# nrf24wifidongle.net
KiCad netlist of a schematic drawn in EAGLE
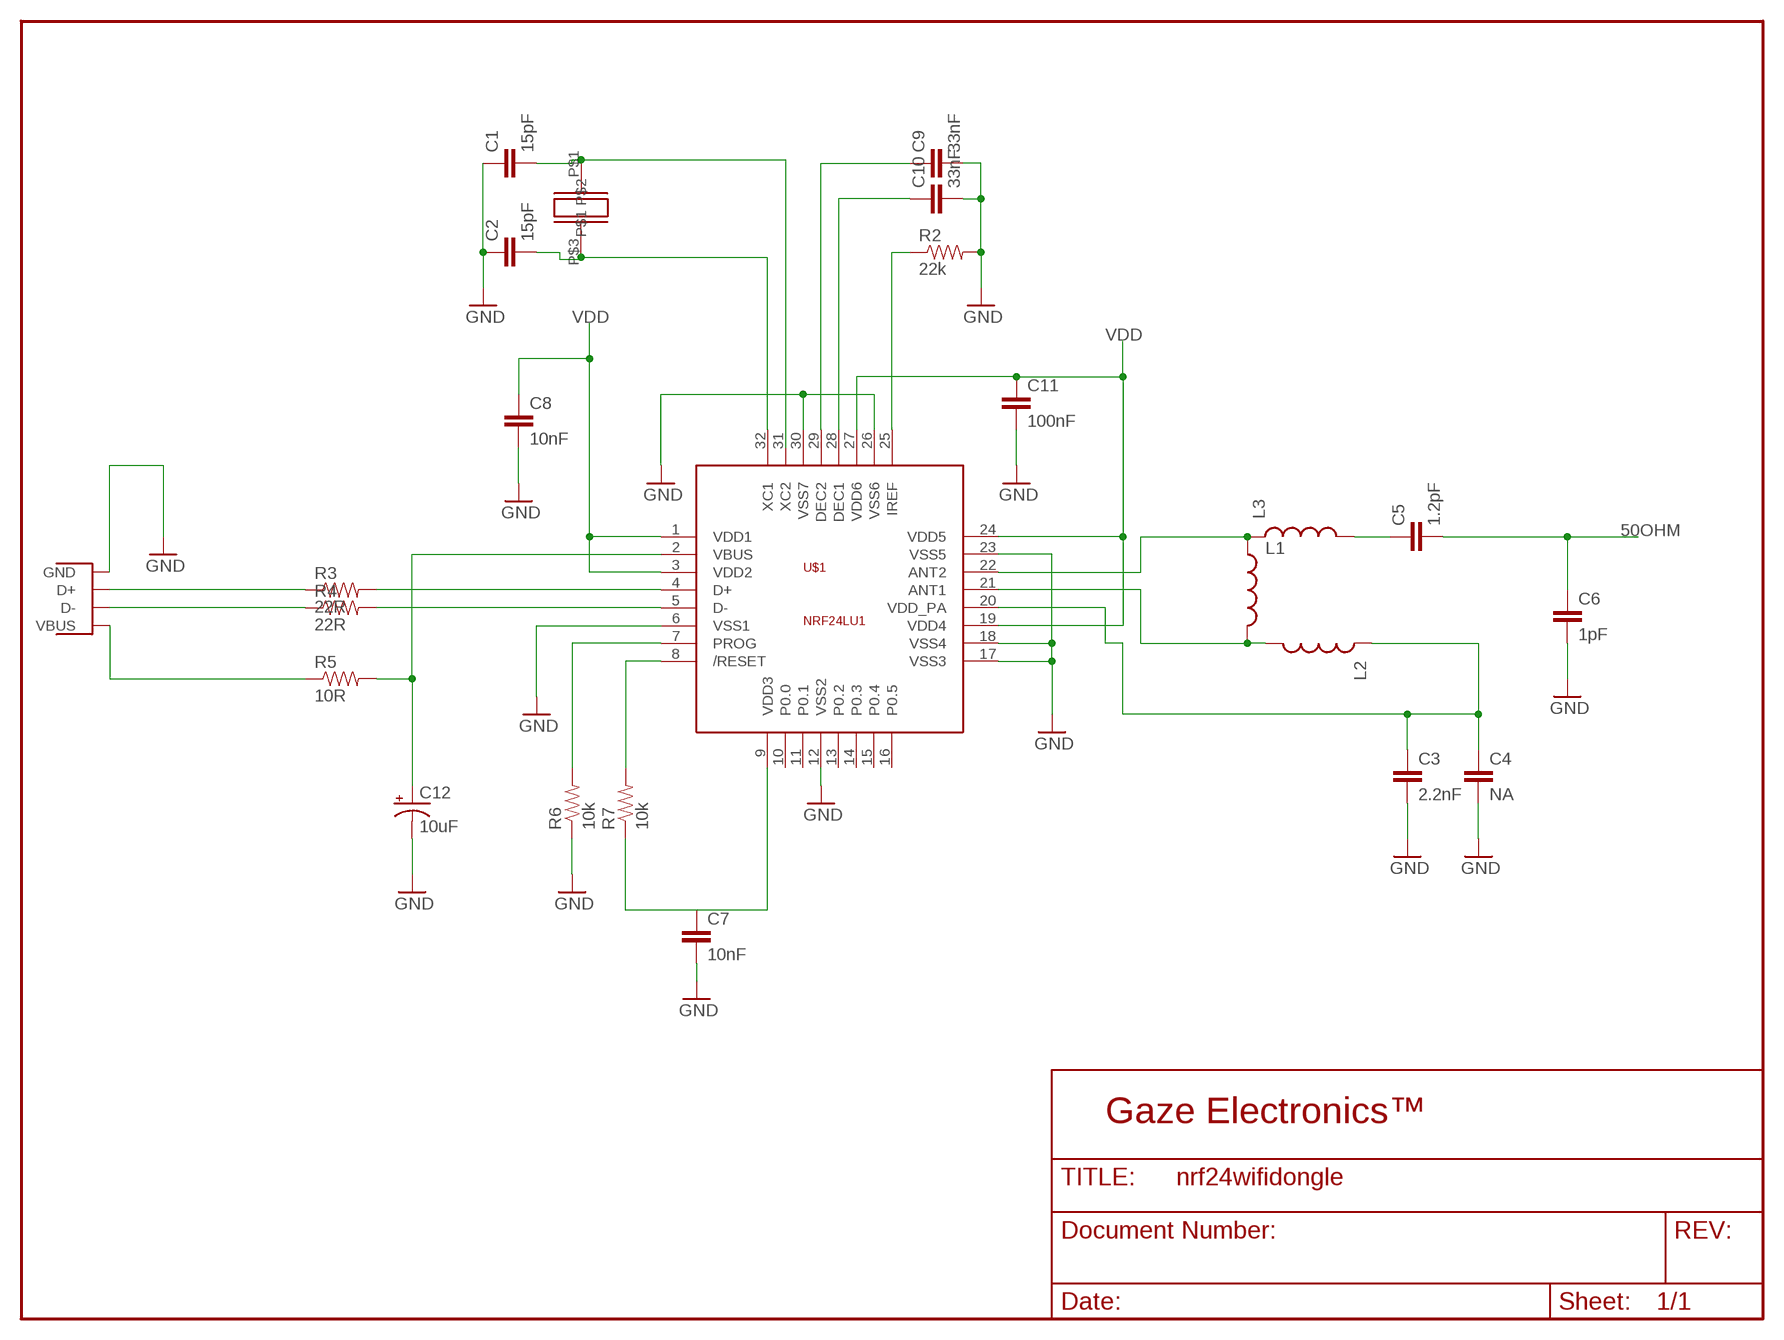
[diagram p0: schematic, sheet 1]

(export (version "E")
  (design (tool "Eeschema 10.0.6"))
  (components
    (comp (ref "C1")
      (value "15pF")
      (footprint "eagle-import:C0402")
      (libsource (lib "eagle-import") (part "CAP0402"))
    )
    (comp (ref "C2")
      (value "15pF")
      (footprint "eagle-import:C0402")
      (libsource (lib "eagle-import") (part "CAP0402"))
    )
    (comp (ref "C3")
      (value "2.2nF")
      (footprint "eagle-import:C0402")
      (libsource (lib "eagle-import") (part "CAP0402"))
    )
    (comp (ref "C4")
      (value "NA")
      (footprint "eagle-import:C0402")
      (libsource (lib "eagle-import") (part "CAP0402"))
    )
    (comp (ref "C5")
      (value "1.2pF")
      (footprint "eagle-import:C0402")
      (libsource (lib "eagle-import") (part "CAP0402"))
    )
    (comp (ref "C6")
      (value "1pF")
      (footprint "eagle-import:C0402")
      (libsource (lib "eagle-import") (part "CAP0402"))
    )
    (comp (ref "C7")
      (value "10nF")
      (footprint "eagle-import:C0402")
      (libsource (lib "eagle-import") (part "CAP0402"))
    )
    (comp (ref "C8")
      (value "10nF")
      (footprint "eagle-import:C0402")
      (libsource (lib "eagle-import") (part "CAP0402"))
    )
    (comp (ref "C9")
      (value "33nF")
      (footprint "eagle-import:C0402")
      (libsource (lib "eagle-import") (part "CAP0402"))
    )
    (comp (ref "C10")
      (value "33nF")
      (footprint "eagle-import:C0402")
      (libsource (lib "eagle-import") (part "CAP0402"))
    )
    (comp (ref "C11")
      (value "100nF")
      (footprint "eagle-import:C0402")
      (libsource (lib "eagle-import") (part "CAP0402"))
    )
    (comp (ref "C12")
      (value "10uF")
      (footprint "eagle-import:EIA3216")
      (libsource (lib "eagle-import") (part "CAP_POL1206"))
    )
    (comp (ref "L1")
      (value "INDUCTOR0402")
      (footprint "eagle-import:C0402")
      (libsource (lib "eagle-import") (part "INDUCTOR0402"))
    )
    (comp (ref "L2")
      (value "INDUCTOR0402")
      (footprint "eagle-import:C0402")
      (libsource (lib "eagle-import") (part "INDUCTOR0402"))
    )
    (comp (ref "L3")
      (value "INDUCTOR0402")
      (footprint "eagle-import:C0402")
      (libsource (lib "eagle-import") (part "INDUCTOR0402"))
    )
    (comp (ref "R2")
      (value "22k")
      (footprint "eagle-import:0402-RES")
      (libsource (lib "eagle-import") (part "RESISTOR0402-RES"))
    )
    (comp (ref "R3")
      (value "22R")
      (footprint "eagle-import:0402-RES")
      (libsource (lib "eagle-import") (part "RESISTOR0402-RES"))
    )
    (comp (ref "R4")
      (value "22R")
      (footprint "eagle-import:0402-RES")
      (libsource (lib "eagle-import") (part "RESISTOR0402-RES"))
    )
    (comp (ref "R5")
      (value "10R")
      (footprint "eagle-import:0402-RES")
      (libsource (lib "eagle-import") (part "RESISTOR0402-RES"))
    )
    (comp (ref "R6")
      (value "10k")
      (footprint "eagle-import:0402-RES")
      (libsource (lib "eagle-import") (part "RESISTOR0402-RES"))
    )
    (comp (ref "R7")
      (value "10k")
      (footprint "eagle-import:0402-RES")
      (libsource (lib "eagle-import") (part "RESISTOR0402-RES"))
    )
    (comp (ref "U$1")
      (value "NRF24LU1")
      (footprint "eagle-import:QFN-32")
      (libsource (lib "eagle-import") (part "NRF24LU1"))
    )
    (comp (ref "U$2")
      (value "CFPX180")
      (footprint "eagle-import:CFPX180")
      (libsource (lib "eagle-import") (part "CFPX180"))
    )
    (comp (ref "X1")
      (value "USBPTH")
      (footprint "eagle-import:USB-B-PTH")
      (libsource (lib "eagle-import") (part "USBPTH"))
    )
  )
  (nets
    (net (code "1") (name "/50OHM") (class "Default")
      (node (ref "C5") (pin "2") (pinfunction "2_2") (pintype "passive"))
      (node (ref "C6") (pin "1") (pinfunction "1_1") (pintype "passive"))
    )
    (net (code "2") (name "/VDD") (class "Default")
      (node (ref "C11") (pin "1") (pinfunction "1_1") (pintype "passive"))
      (node (ref "C8") (pin "1") (pinfunction "1_1") (pintype "passive"))
      (node (ref "U$1") (pin "1") (pinfunction "VDD1_1") (pintype "bidirectional"))
      (node (ref "U$1") (pin "19") (pinfunction "VDD4_19") (pintype "bidirectional"))
      (node (ref "U$1") (pin "24") (pinfunction "VDD5_24") (pintype "bidirectional"))
      (node (ref "U$1") (pin "27") (pinfunction "VDD6_27") (pintype "bidirectional"))
      (node (ref "U$1") (pin "3") (pinfunction "VDD2_3") (pintype "bidirectional"))
    )
    (net (code "3") (name "GND") (class "Default")
      (node (ref "C1") (pin "1") (pinfunction "1_1") (pintype "passive"))
      (node (ref "C10") (pin "2") (pinfunction "2_2") (pintype "passive"))
      (node (ref "C11") (pin "2") (pinfunction "2_2") (pintype "passive"))
      (node (ref "C12") (pin "C") (pinfunction "-_C") (pintype "passive"))
      (node (ref "C2") (pin "1") (pinfunction "1_1") (pintype "passive"))
      (node (ref "C3") (pin "2") (pinfunction "2_2") (pintype "passive"))
      (node (ref "C4") (pin "2") (pinfunction "2_2") (pintype "passive"))
      (node (ref "C6") (pin "2") (pinfunction "2_2") (pintype "passive"))
      (node (ref "C7") (pin "2") (pinfunction "2_2") (pintype "passive"))
      (node (ref "C8") (pin "2") (pinfunction "2_2") (pintype "passive"))
      (node (ref "C9") (pin "2") (pinfunction "2_2") (pintype "passive"))
      (node (ref "R2") (pin "2") (pinfunction "2_2") (pintype "passive"))
      (node (ref "R6") (pin "1") (pinfunction "1_1") (pintype "passive"))
      (node (ref "U$1") (pin "12") (pinfunction "VSS2_12") (pintype "bidirectional"))
      (node (ref "U$1") (pin "17") (pinfunction "VSS3_17") (pintype "bidirectional"))
      (node (ref "U$1") (pin "18") (pinfunction "VSS4_18") (pintype "bidirectional"))
      (node (ref "U$1") (pin "23") (pinfunction "VSS5_23") (pintype "bidirectional"))
      (node (ref "U$1") (pin "26") (pinfunction "VSS6_26") (pintype "bidirectional"))
      (node (ref "U$1") (pin "30") (pinfunction "VSS7_30") (pintype "bidirectional"))
      (node (ref "U$1") (pin "6") (pinfunction "VSS1_6") (pintype "bidirectional"))
      (node (ref "X1") (pin "GND") (pinfunction "GND_GND") (pintype "bidirectional"))
    )
    (net (code "4") (name "Net-(C1-Pad2)") (class "Default")
      (node (ref "C1") (pin "2") (pinfunction "2_2") (pintype "passive"))
      (node (ref "U$2") (pin "P$1") (pinfunction "P$1_P$1") (pintype "bidirectional"))
    )
    (net (code "5") (name "Net-(C5-Pad1)") (class "Default")
      (node (ref "C5") (pin "1") (pinfunction "1_1") (pintype "passive"))
      (node (ref "L3") (pin "2") (pinfunction "2_2") (pintype "passive"))
    )
    (net (code "6") (name "Net-(C12-+)") (class "Default")
      (node (ref "C12") (pin "A") (pinfunction "+_A") (pintype "passive"))
      (node (ref "R5") (pin "2") (pinfunction "2_2") (pintype "passive"))
      (node (ref "U$1") (pin "2") (pinfunction "VBUS_2") (pintype "bidirectional"))
    )
    (net (code "7") (name "Net-(R3-Pad1)") (class "Default")
      (node (ref "R3") (pin "1") (pinfunction "1_1") (pintype "passive"))
      (node (ref "X1") (pin "D+") (pinfunction "D+_D+") (pintype "bidirectional"))
    )
    (net (code "8") (name "Net-(R4-Pad1)") (class "Default")
      (node (ref "R4") (pin "1") (pinfunction "1_1") (pintype "passive"))
      (node (ref "X1") (pin "D-") (pinfunction "D-_D-") (pintype "bidirectional"))
    )
    (net (code "9") (name "Net-(R5-Pad1)") (class "Default")
      (node (ref "R5") (pin "1") (pinfunction "1_1") (pintype "passive"))
      (node (ref "X1") (pin "VBUS") (pinfunction "VBUS_VBUS") (pintype "bidirectional"))
    )
    (net (code "10") (name "Net-(U$1-ANT1)") (class "Default")
      (node (ref "L1") (pin "2") (pinfunction "2_2") (pintype "passive"))
      (node (ref "L2") (pin "2") (pinfunction "2_2") (pintype "passive"))
      (node (ref "U$1") (pin "21") (pinfunction "ANT1_21") (pintype "bidirectional"))
    )
    (net (code "11") (name "Net-(U$1-ANT2)") (class "Default")
      (node (ref "L1") (pin "1") (pinfunction "1_1") (pintype "passive"))
      (node (ref "L3") (pin "1") (pinfunction "1_1") (pintype "passive"))
      (node (ref "U$1") (pin "22") (pinfunction "ANT2_22") (pintype "bidirectional"))
    )
    (net (code "12") (name "Net-(U$1-D+)") (class "Default")
      (node (ref "R3") (pin "2") (pinfunction "2_2") (pintype "passive"))
      (node (ref "U$1") (pin "4") (pinfunction "D+_4") (pintype "bidirectional"))
    )
    (net (code "13") (name "Net-(U$1-D-)") (class "Default")
      (node (ref "R4") (pin "2") (pinfunction "2_2") (pintype "passive"))
      (node (ref "U$1") (pin "5") (pinfunction "D-_5") (pintype "bidirectional"))
    )
    (net (code "14") (name "Net-(U$1-DEC1)") (class "Default")
      (node (ref "C10") (pin "1") (pinfunction "1_1") (pintype "passive"))
      (node (ref "U$1") (pin "28") (pinfunction "DEC1_28") (pintype "bidirectional"))
    )
    (net (code "15") (name "Net-(U$1-DEC2)") (class "Default")
      (node (ref "C9") (pin "1") (pinfunction "1_1") (pintype "passive"))
      (node (ref "U$1") (pin "29") (pinfunction "DEC2_29") (pintype "bidirectional"))
    )
    (net (code "16") (name "Net-(U$1-IREF)") (class "Default")
      (node (ref "R2") (pin "1") (pinfunction "1_1") (pintype "passive"))
      (node (ref "U$1") (pin "25") (pinfunction "IREF_25") (pintype "bidirectional"))
    )
    (net (code "17") (name "Net-(U$1-PROG)") (class "Default")
      (node (ref "R6") (pin "2") (pinfunction "2_2") (pintype "passive"))
      (node (ref "U$1") (pin "7") (pinfunction "PROG_7") (pintype "bidirectional"))
    )
    (net (code "18") (name "Net-(U$1-VDD3)") (class "Default")
      (node (ref "R7") (pin "1") (pinfunction "1_1") (pintype "passive"))
      (node (ref "U$1") (pin "9") (pinfunction "VDD3_9") (pintype "bidirectional"))
    )
    (net (code "19") (name "Net-(U$1-VDD_PA)") (class "Default")
      (node (ref "C3") (pin "1") (pinfunction "1_1") (pintype "passive"))
      (node (ref "C4") (pin "1") (pinfunction "1_1") (pintype "passive"))
      (node (ref "L2") (pin "1") (pinfunction "1_1") (pintype "passive"))
      (node (ref "U$1") (pin "20") (pinfunction "VDD_PA_20") (pintype "bidirectional"))
    )
    (net (code "20") (name "Net-(U$1-XC1)") (class "Default")
      (node (ref "C2") (pin "2") (pinfunction "2_2") (pintype "passive"))
      (node (ref "U$1") (pin "32") (pinfunction "XC1_32") (pintype "bidirectional"))
      (node (ref "U$2") (pin "P$3") (pinfunction "P$2_P$3") (pintype "bidirectional"))
    )
    (net (code "21") (name "Net-(U$1-{slash}RESET)") (class "Default")
      (node (ref "R7") (pin "2") (pinfunction "2_2") (pintype "passive"))
      (node (ref "U$1") (pin "8") (pinfunction "/RESET_8") (pintype "bidirectional"))
    )
    (net (code "22") (name "unconnected-(C7-Pad1)") (class "Default")
      (node (ref "C7") (pin "1") (pinfunction "1_1") (pintype "passive"))
    )
    (net (code "23") (name "unconnected-(U$1-P0.0-Pad10)") (class "Default")
      (node (ref "U$1") (pin "10") (pinfunction "P0.0_10") (pintype "bidirectional"))
    )
    (net (code "24") (name "unconnected-(U$1-P0.1-Pad11)") (class "Default")
      (node (ref "U$1") (pin "11") (pinfunction "P0.1_11") (pintype "bidirectional"))
    )
    (net (code "25") (name "unconnected-(U$1-P0.2-Pad13)") (class "Default")
      (node (ref "U$1") (pin "13") (pinfunction "P0.2_13") (pintype "bidirectional"))
    )
    (net (code "26") (name "unconnected-(U$1-P0.3-Pad14)") (class "Default")
      (node (ref "U$1") (pin "14") (pinfunction "P0.3_14") (pintype "bidirectional"))
    )
    (net (code "27") (name "unconnected-(U$1-P0.4-Pad15)") (class "Default")
      (node (ref "U$1") (pin "15") (pinfunction "P0.4_15") (pintype "bidirectional"))
    )
    (net (code "28") (name "unconnected-(U$1-P0.5-Pad16)") (class "Default")
      (node (ref "U$1") (pin "16") (pinfunction "P0.5_16") (pintype "bidirectional"))
    )
    (net (code "29") (name "unconnected-(U$1-XC2-Pad31)") (class "Default")
      (node (ref "U$1") (pin "31") (pinfunction "XC2_31") (pintype "bidirectional"))
    )
  )
)
